# IO60P16.net
KiCad netlist of a schematic drawn in EAGLE
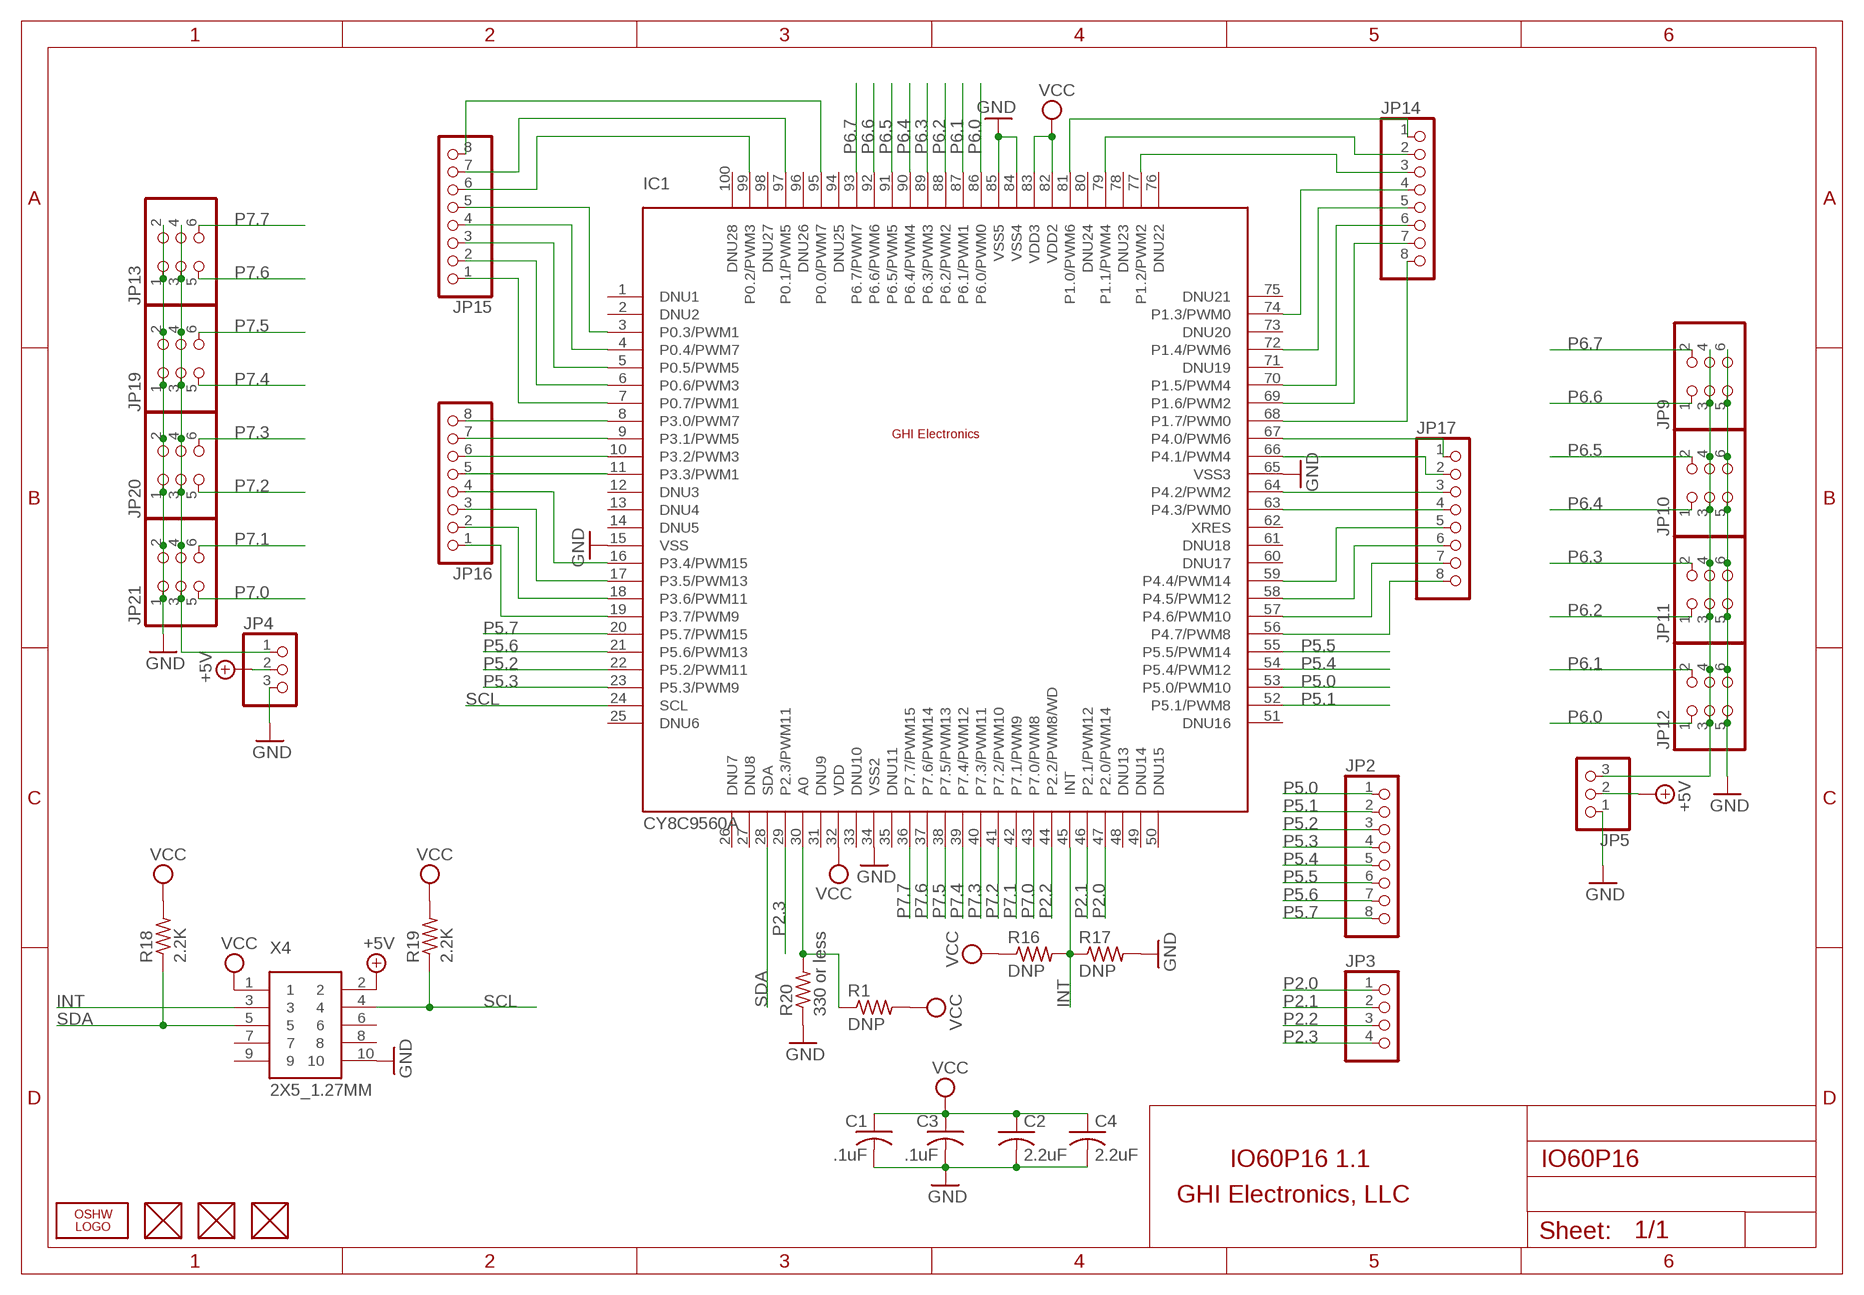
[diagram p0: schematic, sheet 1]

(export (version "E")
  (design (tool "Eeschema 10.0.6"))
  (components
    (comp (ref "C1")
      (value ".1uF")
      (footprint "eagle-import:C0603K")
      (libsource (lib "eagle-import") (part "C-USC0603K"))
    )
    (comp (ref "C2")
      (value "2.2uF")
      (footprint "eagle-import:C0805K")
      (libsource (lib "eagle-import") (part "C-USC0805K"))
    )
    (comp (ref "C3")
      (value ".1uF")
      (footprint "eagle-import:C0603K")
      (libsource (lib "eagle-import") (part "C-USC0603K"))
    )
    (comp (ref "C4")
      (value "2.2uF")
      (footprint "eagle-import:C0805K")
      (libsource (lib "eagle-import") (part "C-USC0805K"))
    )
    (comp (ref "FUD1")
      (value "FIDUCIAL")
      (footprint "eagle-import:FIDUCIAL_40MIL")
      (libsource (lib "eagle-import") (part "FIDUCIAL"))
    )
    (comp (ref "FUD2")
      (value "FIDUCIAL")
      (footprint "eagle-import:FIDUCIAL_40MIL")
      (libsource (lib "eagle-import") (part "FIDUCIAL"))
    )
    (comp (ref "FUD3")
      (value "FIDUCIAL")
      (footprint "eagle-import:FIDUCIAL_40MIL")
      (libsource (lib "eagle-import") (part "FIDUCIAL"))
    )
    (comp (ref "IC1")
      (value "CY8C9560A")
      (footprint "eagle-import:LQFP100")
      (libsource (lib "eagle-import") (part "CY8C9560A"))
    )
    (comp (ref "JP2")
      (value "PINHD-1X8")
      (footprint "eagle-import:1X08")
      (libsource (lib "eagle-import") (part "PINHD-1X8"))
    )
    (comp (ref "JP3")
      (value "PINHD-1X4")
      (footprint "eagle-import:1X04")
      (libsource (lib "eagle-import") (part "PINHD-1X4"))
    )
    (comp (ref "JP4")
      (value "PINHD-1X3")
      (footprint "eagle-import:1X03")
      (libsource (lib "eagle-import") (part "PINHD-1X3"))
    )
    (comp (ref "JP5")
      (value "PINHD-1X3")
      (footprint "eagle-import:1X03")
      (libsource (lib "eagle-import") (part "PINHD-1X3"))
    )
    (comp (ref "JP9")
      (value "PINHD-2X3")
      (footprint "eagle-import:2X03")
      (libsource (lib "eagle-import") (part "PINHD-2X3"))
    )
    (comp (ref "JP10")
      (value "PINHD-2X3")
      (footprint "eagle-import:2X03")
      (libsource (lib "eagle-import") (part "PINHD-2X3"))
    )
    (comp (ref "JP11")
      (value "PINHD-2X3")
      (footprint "eagle-import:2X03")
      (libsource (lib "eagle-import") (part "PINHD-2X3"))
    )
    (comp (ref "JP12")
      (value "PINHD-2X3")
      (footprint "eagle-import:2X03")
      (libsource (lib "eagle-import") (part "PINHD-2X3"))
    )
    (comp (ref "JP13")
      (value "PINHD-2X3")
      (footprint "eagle-import:2X03")
      (libsource (lib "eagle-import") (part "PINHD-2X3"))
    )
    (comp (ref "JP14")
      (value "PINHD-1X8")
      (footprint "eagle-import:1X08")
      (libsource (lib "eagle-import") (part "PINHD-1X8"))
    )
    (comp (ref "JP15")
      (value "PINHD-1X8")
      (footprint "eagle-import:1X08")
      (libsource (lib "eagle-import") (part "PINHD-1X8"))
    )
    (comp (ref "JP16")
      (value "PINHD-1X8")
      (footprint "eagle-import:1X08")
      (libsource (lib "eagle-import") (part "PINHD-1X8"))
    )
    (comp (ref "JP17")
      (value "PINHD-1X8")
      (footprint "eagle-import:1X08")
      (libsource (lib "eagle-import") (part "PINHD-1X8"))
    )
    (comp (ref "JP19")
      (value "PINHD-2X3")
      (footprint "eagle-import:2X03")
      (libsource (lib "eagle-import") (part "PINHD-2X3"))
    )
    (comp (ref "JP20")
      (value "PINHD-2X3")
      (footprint "eagle-import:2X03")
      (libsource (lib "eagle-import") (part "PINHD-2X3"))
    )
    (comp (ref "JP21")
      (value "PINHD-2X3")
      (footprint "eagle-import:2X03")
      (libsource (lib "eagle-import") (part "PINHD-2X3"))
    )
    (comp (ref "LOGO1")
      (value "LOGO-OSHW-FILLX0200-NT")
      (footprint "eagle-import:OSHW_FILLX200_NOTEXT")
      (libsource (lib "eagle-import") (part "LOGO-OSHW-FILLX0200-NT"))
    )
    (comp (ref "R1")
      (value "DNP")
      (footprint "eagle-import:R0603")
      (libsource (lib "eagle-import") (part "R-US_R0603"))
    )
    (comp (ref "R16")
      (value "DNP")
      (footprint "eagle-import:R0603")
      (libsource (lib "eagle-import") (part "R-US_R0603"))
    )
    (comp (ref "R17")
      (value "DNP")
      (footprint "eagle-import:R0603")
      (libsource (lib "eagle-import") (part "R-US_R0603"))
    )
    (comp (ref "R18")
      (value "2.2K")
      (footprint "eagle-import:R0603")
      (libsource (lib "eagle-import") (part "R-US_R0603"))
    )
    (comp (ref "R19")
      (value "2.2K")
      (footprint "eagle-import:R0603")
      (libsource (lib "eagle-import") (part "R-US_R0603"))
    )
    (comp (ref "R20")
      (value "330 or less")
      (footprint "eagle-import:R0603")
      (libsource (lib "eagle-import") (part "R-US_R0603"))
    )
    (comp (ref "X4")
      (value "2X5_1.27MM")
      (footprint "eagle-import:2X5_1.27MM")
      (libsource (lib "eagle-import") (part "2X5_1.27MM"))
    )
  )
  (nets
    (net (code "1") (name "+5V") (class "Default")
      (node (ref "JP4") (pin "2") (pinfunction "2_2") (pintype "passive"))
      (node (ref "JP5") (pin "2") (pinfunction "2_2") (pintype "passive"))
      (node (ref "X4") (pin "2") (pinfunction "2_2") (pintype "bidirectional"))
    )
    (net (code "2") (name "/INT") (class "Default")
      (node (ref "IC1") (pin "45") (pinfunction "INT_45") (pintype "bidirectional"))
      (node (ref "R16") (pin "2") (pinfunction "2_2") (pintype "passive"))
      (node (ref "R17") (pin "1") (pinfunction "1_1") (pintype "passive"))
      (node (ref "X4") (pin "3") (pinfunction "3_3") (pintype "bidirectional"))
    )
    (net (code "3") (name "/P2.0") (class "Default")
      (node (ref "IC1") (pin "47") (pinfunction "P2.0/PWM14_47") (pintype "bidirectional"))
      (node (ref "JP3") (pin "1") (pinfunction "1_1") (pintype "passive"))
    )
    (net (code "4") (name "/P2.1") (class "Default")
      (node (ref "IC1") (pin "46") (pinfunction "P2.1/PWM12_46") (pintype "bidirectional"))
      (node (ref "JP3") (pin "2") (pinfunction "2_2") (pintype "passive"))
    )
    (net (code "5") (name "/P2.2") (class "Default")
      (node (ref "IC1") (pin "44") (pinfunction "P2.2/PWM8/WD_44") (pintype "bidirectional"))
      (node (ref "JP3") (pin "3") (pinfunction "3_3") (pintype "passive"))
    )
    (net (code "6") (name "/P2.3") (class "Default")
      (node (ref "IC1") (pin "29") (pinfunction "P2.3/PWM11_29") (pintype "bidirectional"))
      (node (ref "JP3") (pin "4") (pinfunction "4_4") (pintype "passive"))
    )
    (net (code "7") (name "/P5.0") (class "Default")
      (node (ref "IC1") (pin "53") (pinfunction "P5.0/PWM10_53") (pintype "bidirectional"))
      (node (ref "JP2") (pin "1") (pinfunction "1_1") (pintype "passive"))
    )
    (net (code "8") (name "/P5.1") (class "Default")
      (node (ref "IC1") (pin "52") (pinfunction "P5.1/PWM8_52") (pintype "bidirectional"))
      (node (ref "JP2") (pin "2") (pinfunction "2_2") (pintype "passive"))
    )
    (net (code "9") (name "/P5.2") (class "Default")
      (node (ref "IC1") (pin "22") (pinfunction "P5.2/PWM11_22") (pintype "bidirectional"))
      (node (ref "JP2") (pin "3") (pinfunction "3_3") (pintype "passive"))
    )
    (net (code "10") (name "/P5.3") (class "Default")
      (node (ref "IC1") (pin "23") (pinfunction "P5.3/PWM9_23") (pintype "bidirectional"))
      (node (ref "JP2") (pin "4") (pinfunction "4_4") (pintype "passive"))
    )
    (net (code "11") (name "/P5.4") (class "Default")
      (node (ref "IC1") (pin "54") (pinfunction "P5.4/PWM12_54") (pintype "bidirectional"))
      (node (ref "JP2") (pin "5") (pinfunction "5_5") (pintype "passive"))
    )
    (net (code "12") (name "/P5.5") (class "Default")
      (node (ref "IC1") (pin "55") (pinfunction "P5.5/PWM14_55") (pintype "bidirectional"))
      (node (ref "JP2") (pin "6") (pinfunction "6_6") (pintype "passive"))
    )
    (net (code "13") (name "/P5.6") (class "Default")
      (node (ref "IC1") (pin "21") (pinfunction "P5.6/PWM13_21") (pintype "bidirectional"))
      (node (ref "JP2") (pin "7") (pinfunction "7_7") (pintype "passive"))
    )
    (net (code "14") (name "/P5.7") (class "Default")
      (node (ref "IC1") (pin "20") (pinfunction "P5.7/PWM15_20") (pintype "bidirectional"))
      (node (ref "JP2") (pin "8") (pinfunction "8_8") (pintype "passive"))
    )
    (net (code "15") (name "/P6.0") (class "Default")
      (node (ref "IC1") (pin "86") (pinfunction "P6.0/PWM0_86") (pintype "bidirectional"))
      (node (ref "JP12") (pin "1") (pinfunction "1_1") (pintype "passive"))
    )
    (net (code "16") (name "/P6.1") (class "Default")
      (node (ref "IC1") (pin "87") (pinfunction "P6.1/PWM1_87") (pintype "bidirectional"))
      (node (ref "JP12") (pin "2") (pinfunction "2_2") (pintype "passive"))
    )
    (net (code "17") (name "/P6.2") (class "Default")
      (node (ref "IC1") (pin "88") (pinfunction "P6.2/PWM2_88") (pintype "bidirectional"))
      (node (ref "JP11") (pin "1") (pinfunction "1_1") (pintype "passive"))
    )
    (net (code "18") (name "/P6.3") (class "Default")
      (node (ref "IC1") (pin "89") (pinfunction "P6.3/PWM3_89") (pintype "bidirectional"))
      (node (ref "JP11") (pin "2") (pinfunction "2_2") (pintype "passive"))
    )
    (net (code "19") (name "/P6.4") (class "Default")
      (node (ref "IC1") (pin "90") (pinfunction "P6.4/PWM4_90") (pintype "bidirectional"))
      (node (ref "JP10") (pin "1") (pinfunction "1_1") (pintype "passive"))
    )
    (net (code "20") (name "/P6.5") (class "Default")
      (node (ref "IC1") (pin "91") (pinfunction "P6.5/PWM5_91") (pintype "bidirectional"))
      (node (ref "JP10") (pin "2") (pinfunction "2_2") (pintype "passive"))
    )
    (net (code "21") (name "/P6.6") (class "Default")
      (node (ref "IC1") (pin "92") (pinfunction "P6.6/PWM6_92") (pintype "bidirectional"))
      (node (ref "JP9") (pin "1") (pinfunction "1_1") (pintype "passive"))
    )
    (net (code "22") (name "/P6.7") (class "Default")
      (node (ref "IC1") (pin "93") (pinfunction "P6.7/PWM7_93") (pintype "bidirectional"))
      (node (ref "JP9") (pin "2") (pinfunction "2_2") (pintype "passive"))
    )
    (net (code "23") (name "/P7.0") (class "Default")
      (node (ref "IC1") (pin "43") (pinfunction "P7.0/PWM8_43") (pintype "bidirectional"))
      (node (ref "JP21") (pin "5") (pinfunction "5_5") (pintype "passive"))
    )
    (net (code "24") (name "/P7.1") (class "Default")
      (node (ref "IC1") (pin "42") (pinfunction "P7.1/PWM9_42") (pintype "bidirectional"))
      (node (ref "JP21") (pin "6") (pinfunction "6_6") (pintype "passive"))
    )
    (net (code "25") (name "/P7.2") (class "Default")
      (node (ref "IC1") (pin "41") (pinfunction "P7.2/PWM10_41") (pintype "bidirectional"))
      (node (ref "JP20") (pin "5") (pinfunction "5_5") (pintype "passive"))
    )
    (net (code "26") (name "/P7.3") (class "Default")
      (node (ref "IC1") (pin "40") (pinfunction "P7.3/PWM11_40") (pintype "bidirectional"))
      (node (ref "JP20") (pin "6") (pinfunction "6_6") (pintype "passive"))
    )
    (net (code "27") (name "/P7.4") (class "Default")
      (node (ref "IC1") (pin "39") (pinfunction "P7.4/PWM12_39") (pintype "bidirectional"))
      (node (ref "JP19") (pin "5") (pinfunction "5_5") (pintype "passive"))
    )
    (net (code "28") (name "/P7.5") (class "Default")
      (node (ref "IC1") (pin "38") (pinfunction "P7.5/PWM13_38") (pintype "bidirectional"))
      (node (ref "JP19") (pin "6") (pinfunction "6_6") (pintype "passive"))
    )
    (net (code "29") (name "/P7.6") (class "Default")
      (node (ref "IC1") (pin "37") (pinfunction "P7.6/PWM14_37") (pintype "bidirectional"))
      (node (ref "JP13") (pin "5") (pinfunction "5_5") (pintype "passive"))
    )
    (net (code "30") (name "/P7.7") (class "Default")
      (node (ref "IC1") (pin "36") (pinfunction "P7.7/PWM15_36") (pintype "bidirectional"))
      (node (ref "JP13") (pin "6") (pinfunction "6_6") (pintype "passive"))
    )
    (net (code "31") (name "/SCL") (class "Default")
      (node (ref "IC1") (pin "24") (pinfunction "SCL_24") (pintype "bidirectional"))
      (node (ref "R19") (pin "1") (pinfunction "1_1") (pintype "passive"))
      (node (ref "X4") (pin "4") (pinfunction "4_4") (pintype "bidirectional"))
    )
    (net (code "32") (name "/SDA") (class "Default")
      (node (ref "IC1") (pin "28") (pinfunction "SDA_28") (pintype "bidirectional"))
      (node (ref "R18") (pin "1") (pinfunction "1_1") (pintype "passive"))
      (node (ref "X4") (pin "5") (pinfunction "5_5") (pintype "bidirectional"))
    )
    (net (code "33") (name "GND") (class "Default")
      (node (ref "C1") (pin "2") (pinfunction "2_2") (pintype "passive"))
      (node (ref "C2") (pin "2") (pinfunction "2_2") (pintype "passive"))
      (node (ref "C3") (pin "2") (pinfunction "2_2") (pintype "passive"))
      (node (ref "C4") (pin "2") (pinfunction "2_2") (pintype "passive"))
      (node (ref "IC1") (pin "15") (pinfunction "VSS_15") (pintype "bidirectional"))
      (node (ref "IC1") (pin "34") (pinfunction "VSS2_34") (pintype "bidirectional"))
      (node (ref "IC1") (pin "65") (pinfunction "VSS3_65") (pintype "bidirectional"))
      (node (ref "IC1") (pin "84") (pinfunction "VSS4_84") (pintype "bidirectional"))
      (node (ref "IC1") (pin "85") (pinfunction "VSS5_85") (pintype "bidirectional"))
      (node (ref "JP10") (pin "5") (pinfunction "5_5") (pintype "passive"))
      (node (ref "JP10") (pin "6") (pinfunction "6_6") (pintype "passive"))
      (node (ref "JP11") (pin "5") (pinfunction "5_5") (pintype "passive"))
      (node (ref "JP11") (pin "6") (pinfunction "6_6") (pintype "passive"))
      (node (ref "JP12") (pin "5") (pinfunction "5_5") (pintype "passive"))
      (node (ref "JP12") (pin "6") (pinfunction "6_6") (pintype "passive"))
      (node (ref "JP13") (pin "1") (pinfunction "1_1") (pintype "passive"))
      (node (ref "JP13") (pin "2") (pinfunction "2_2") (pintype "passive"))
      (node (ref "JP19") (pin "1") (pinfunction "1_1") (pintype "passive"))
      (node (ref "JP19") (pin "2") (pinfunction "2_2") (pintype "passive"))
      (node (ref "JP20") (pin "1") (pinfunction "1_1") (pintype "passive"))
      (node (ref "JP20") (pin "2") (pinfunction "2_2") (pintype "passive"))
      (node (ref "JP21") (pin "1") (pinfunction "1_1") (pintype "passive"))
      (node (ref "JP21") (pin "2") (pinfunction "2_2") (pintype "passive"))
      (node (ref "JP4") (pin "3") (pinfunction "3_3") (pintype "passive"))
      (node (ref "JP5") (pin "1") (pinfunction "1_1") (pintype "passive"))
      (node (ref "JP9") (pin "5") (pinfunction "5_5") (pintype "passive"))
      (node (ref "JP9") (pin "6") (pinfunction "6_6") (pintype "passive"))
      (node (ref "R17") (pin "2") (pinfunction "2_2") (pintype "passive"))
      (node (ref "R20") (pin "1") (pinfunction "1_1") (pintype "passive"))
      (node (ref "X4") (pin "10") (pinfunction "10_10") (pintype "bidirectional"))
    )
    (net (code "34") (name "Net-(IC1-A0)") (class "Default")
      (node (ref "IC1") (pin "30") (pinfunction "A0_30") (pintype "bidirectional"))
      (node (ref "R1") (pin "1") (pinfunction "1_1") (pintype "passive"))
      (node (ref "R20") (pin "2") (pinfunction "2_2") (pintype "passive"))
    )
    (net (code "35") (name "Net-(IC1-P0.0{slash}PWM7)") (class "Default")
      (node (ref "IC1") (pin "95") (pinfunction "P0.0/PWM7_95") (pintype "bidirectional"))
      (node (ref "JP15") (pin "8") (pinfunction "8_8") (pintype "passive"))
    )
    (net (code "36") (name "Net-(IC1-P0.1{slash}PWM5)") (class "Default")
      (node (ref "IC1") (pin "97") (pinfunction "P0.1/PWM5_97") (pintype "bidirectional"))
      (node (ref "JP15") (pin "7") (pinfunction "7_7") (pintype "passive"))
    )
    (net (code "37") (name "Net-(IC1-P0.2{slash}PWM3)") (class "Default")
      (node (ref "IC1") (pin "99") (pinfunction "P0.2/PWM3_99") (pintype "bidirectional"))
      (node (ref "JP15") (pin "6") (pinfunction "6_6") (pintype "passive"))
    )
    (net (code "38") (name "Net-(IC1-P0.3{slash}PWM1)") (class "Default")
      (node (ref "IC1") (pin "3") (pinfunction "P0.3/PWM1_3") (pintype "bidirectional"))
      (node (ref "JP15") (pin "5") (pinfunction "5_5") (pintype "passive"))
    )
    (net (code "39") (name "Net-(IC1-P0.4{slash}PWM7)") (class "Default")
      (node (ref "IC1") (pin "4") (pinfunction "P0.4/PWM7_4") (pintype "bidirectional"))
      (node (ref "JP15") (pin "4") (pinfunction "4_4") (pintype "passive"))
    )
    (net (code "40") (name "Net-(IC1-P0.5{slash}PWM5)") (class "Default")
      (node (ref "IC1") (pin "5") (pinfunction "P0.5/PWM5_5") (pintype "bidirectional"))
      (node (ref "JP15") (pin "3") (pinfunction "3_3") (pintype "passive"))
    )
    (net (code "41") (name "Net-(IC1-P0.6{slash}PWM3)") (class "Default")
      (node (ref "IC1") (pin "6") (pinfunction "P0.6/PWM3_6") (pintype "bidirectional"))
      (node (ref "JP15") (pin "2") (pinfunction "2_2") (pintype "passive"))
    )
    (net (code "42") (name "Net-(IC1-P0.7{slash}PWM1)") (class "Default")
      (node (ref "IC1") (pin "7") (pinfunction "P0.7/PWM1_7") (pintype "bidirectional"))
      (node (ref "JP15") (pin "1") (pinfunction "1_1") (pintype "passive"))
    )
    (net (code "43") (name "Net-(IC1-P1.0{slash}PWM6)") (class "Default")
      (node (ref "IC1") (pin "81") (pinfunction "P1.0/PWM6_81") (pintype "bidirectional"))
      (node (ref "JP14") (pin "1") (pinfunction "1_1") (pintype "passive"))
    )
    (net (code "44") (name "Net-(IC1-P1.1{slash}PWM4)") (class "Default")
      (node (ref "IC1") (pin "79") (pinfunction "P1.1/PWM4_79") (pintype "bidirectional"))
      (node (ref "JP14") (pin "2") (pinfunction "2_2") (pintype "passive"))
    )
    (net (code "45") (name "Net-(IC1-P1.2{slash}PWM2)") (class "Default")
      (node (ref "IC1") (pin "77") (pinfunction "P1.2/PWM2_77") (pintype "bidirectional"))
      (node (ref "JP14") (pin "3") (pinfunction "3_3") (pintype "passive"))
    )
    (net (code "46") (name "Net-(IC1-P1.3{slash}PWM0)") (class "Default")
      (node (ref "IC1") (pin "74") (pinfunction "P1.3/PWM0_74") (pintype "bidirectional"))
      (node (ref "JP14") (pin "4") (pinfunction "4_4") (pintype "passive"))
    )
    (net (code "47") (name "Net-(IC1-P1.4{slash}PWM6)") (class "Default")
      (node (ref "IC1") (pin "72") (pinfunction "P1.4/PWM6_72") (pintype "bidirectional"))
      (node (ref "JP14") (pin "5") (pinfunction "5_5") (pintype "passive"))
    )
    (net (code "48") (name "Net-(IC1-P1.5{slash}PWM4)") (class "Default")
      (node (ref "IC1") (pin "70") (pinfunction "P1.5/PWM4_70") (pintype "bidirectional"))
      (node (ref "JP14") (pin "6") (pinfunction "6_6") (pintype "passive"))
    )
    (net (code "49") (name "Net-(IC1-P1.6{slash}PWM2)") (class "Default")
      (node (ref "IC1") (pin "69") (pinfunction "P1.6/PWM2_69") (pintype "bidirectional"))
      (node (ref "JP14") (pin "7") (pinfunction "7_7") (pintype "passive"))
    )
    (net (code "50") (name "Net-(IC1-P1.7{slash}PWM0)") (class "Default")
      (node (ref "IC1") (pin "68") (pinfunction "P1.7/PWM0_68") (pintype "bidirectional"))
      (node (ref "JP14") (pin "8") (pinfunction "8_8") (pintype "passive"))
    )
    (net (code "51") (name "Net-(IC1-P3.0{slash}PWM7)") (class "Default")
      (node (ref "IC1") (pin "8") (pinfunction "P3.0/PWM7_8") (pintype "bidirectional"))
      (node (ref "JP16") (pin "8") (pinfunction "8_8") (pintype "passive"))
    )
    (net (code "52") (name "Net-(IC1-P3.1{slash}PWM5)") (class "Default")
      (node (ref "IC1") (pin "9") (pinfunction "P3.1/PWM5_9") (pintype "bidirectional"))
      (node (ref "JP16") (pin "7") (pinfunction "7_7") (pintype "passive"))
    )
    (net (code "53") (name "Net-(IC1-P3.2{slash}PWM3)") (class "Default")
      (node (ref "IC1") (pin "10") (pinfunction "P3.2/PWM3_10") (pintype "bidirectional"))
      (node (ref "JP16") (pin "6") (pinfunction "6_6") (pintype "passive"))
    )
    (net (code "54") (name "Net-(IC1-P3.3{slash}PWM1)") (class "Default")
      (node (ref "IC1") (pin "11") (pinfunction "P3.3/PWM1_11") (pintype "bidirectional"))
      (node (ref "JP16") (pin "5") (pinfunction "5_5") (pintype "passive"))
    )
    (net (code "55") (name "Net-(IC1-P3.4{slash}PWM15)") (class "Default")
      (node (ref "IC1") (pin "16") (pinfunction "P3.4/PWM15_16") (pintype "bidirectional"))
      (node (ref "JP16") (pin "4") (pinfunction "4_4") (pintype "passive"))
    )
    (net (code "56") (name "Net-(IC1-P3.5{slash}PWM13)") (class "Default")
      (node (ref "IC1") (pin "17") (pinfunction "P3.5/PWM13_17") (pintype "bidirectional"))
      (node (ref "JP16") (pin "3") (pinfunction "3_3") (pintype "passive"))
    )
    (net (code "57") (name "Net-(IC1-P3.6{slash}PWM11)") (class "Default")
      (node (ref "IC1") (pin "18") (pinfunction "P3.6/PWM11_18") (pintype "bidirectional"))
      (node (ref "JP16") (pin "2") (pinfunction "2_2") (pintype "passive"))
    )
    (net (code "58") (name "Net-(IC1-P3.7{slash}PWM9)") (class "Default")
      (node (ref "IC1") (pin "19") (pinfunction "P3.7/PWM9_19") (pintype "bidirectional"))
      (node (ref "JP16") (pin "1") (pinfunction "1_1") (pintype "passive"))
    )
    (net (code "59") (name "Net-(IC1-P4.0{slash}PWM6)") (class "Default")
      (node (ref "IC1") (pin "67") (pinfunction "P4.0/PWM6_67") (pintype "bidirectional"))
      (node (ref "JP17") (pin "1") (pinfunction "1_1") (pintype "passive"))
    )
    (net (code "60") (name "Net-(IC1-P4.1{slash}PWM4)") (class "Default")
      (node (ref "IC1") (pin "66") (pinfunction "P4.1/PWM4_66") (pintype "bidirectional"))
      (node (ref "JP17") (pin "2") (pinfunction "2_2") (pintype "passive"))
    )
    (net (code "61") (name "Net-(IC1-P4.2{slash}PWM2)") (class "Default")
      (node (ref "IC1") (pin "64") (pinfunction "P4.2/PWM2_64") (pintype "bidirectional"))
      (node (ref "JP17") (pin "3") (pinfunction "3_3") (pintype "passive"))
    )
    (net (code "62") (name "Net-(IC1-P4.3{slash}PWM0)") (class "Default")
      (node (ref "IC1") (pin "63") (pinfunction "P4.3/PWM0_63") (pintype "bidirectional"))
      (node (ref "JP17") (pin "4") (pinfunction "4_4") (pintype "passive"))
    )
    (net (code "63") (name "Net-(IC1-P4.4{slash}PWM14)") (class "Default")
      (node (ref "IC1") (pin "59") (pinfunction "P4.4/PWM14_59") (pintype "bidirectional"))
      (node (ref "JP17") (pin "5") (pinfunction "5_5") (pintype "passive"))
    )
    (net (code "64") (name "Net-(IC1-P4.5{slash}PWM12)") (class "Default")
      (node (ref "IC1") (pin "58") (pinfunction "P4.5/PWM12_58") (pintype "bidirectional"))
      (node (ref "JP17") (pin "6") (pinfunction "6_6") (pintype "passive"))
    )
    (net (code "65") (name "Net-(IC1-P4.6{slash}PWM10)") (class "Default")
      (node (ref "IC1") (pin "57") (pinfunction "P4.6/PWM10_57") (pintype "bidirectional"))
      (node (ref "JP17") (pin "7") (pinfunction "7_7") (pintype "passive"))
    )
    (net (code "66") (name "Net-(IC1-P4.7{slash}PWM8)") (class "Default")
      (node (ref "IC1") (pin "56") (pinfunction "P4.7/PWM8_56") (pintype "bidirectional"))
      (node (ref "JP17") (pin "8") (pinfunction "8_8") (pintype "passive"))
    )
    (net (code "67") (name "Net-(JP10-Pad3)") (class "Default")
      (node (ref "JP10") (pin "3") (pinfunction "3_3") (pintype "passive"))
      (node (ref "JP10") (pin "4") (pinfunction "4_4") (pintype "passive"))
      (node (ref "JP11") (pin "3") (pinfunction "3_3") (pintype "passive"))
      (node (ref "JP11") (pin "4") (pinfunction "4_4") (pintype "passive"))
      (node (ref "JP12") (pin "3") (pinfunction "3_3") (pintype "passive"))
      (node (ref "JP12") (pin "4") (pinfunction "4_4") (pintype "passive"))
      (node (ref "JP5") (pin "3") (pinfunction "3_3") (pintype "passive"))
      (node (ref "JP9") (pin "3") (pinfunction "3_3") (pintype "passive"))
      (node (ref "JP9") (pin "4") (pinfunction "4_4") (pintype "passive"))
    )
    (net (code "68") (name "Net-(JP13-Pad3)") (class "Default")
      (node (ref "JP13") (pin "3") (pinfunction "3_3") (pintype "passive"))
      (node (ref "JP13") (pin "4") (pinfunction "4_4") (pintype "passive"))
      (node (ref "JP19") (pin "3") (pinfunction "3_3") (pintype "passive"))
      (node (ref "JP19") (pin "4") (pinfunction "4_4") (pintype "passive"))
      (node (ref "JP20") (pin "3") (pinfunction "3_3") (pintype "passive"))
      (node (ref "JP20") (pin "4") (pinfunction "4_4") (pintype "passive"))
      (node (ref "JP21") (pin "3") (pinfunction "3_3") (pintype "passive"))
      (node (ref "JP21") (pin "4") (pinfunction "4_4") (pintype "passive"))
      (node (ref "JP4") (pin "1") (pinfunction "1_1") (pintype "passive"))
    )
    (net (code "69") (name "VCC") (class "Default")
      (node (ref "C1") (pin "1") (pinfunction "1_1") (pintype "passive"))
      (node (ref "C2") (pin "1") (pinfunction "1_1") (pintype "passive"))
      (node (ref "C3") (pin "1") (pinfunction "1_1") (pintype "passive"))
      (node (ref "C4") (pin "1") (pinfunction "1_1") (pintype "passive"))
      (node (ref "IC1") (pin "32") (pinfunction "VDD_32") (pintype "bidirectional"))
      (node (ref "IC1") (pin "82") (pinfunction "VDD2_82") (pintype "bidirectional"))
      (node (ref "IC1") (pin "83") (pinfunction "VDD3_83") (pintype "bidirectional"))
      (node (ref "R1") (pin "2") (pinfunction "2_2") (pintype "passive"))
      (node (ref "R16") (pin "1") (pinfunction "1_1") (pintype "passive"))
      (node (ref "R18") (pin "2") (pinfunction "2_2") (pintype "passive"))
      (node (ref "R19") (pin "2") (pinfunction "2_2") (pintype "passive"))
      (node (ref "X4") (pin "1") (pinfunction "1_1") (pintype "bidirectional"))
    )
    (net (code "70") (name "unconnected-(FUD1-PadP$1)") (class "Default")
      (node (ref "FUD1") (pin "P$1") (pinfunction "P$1_P$1") (pintype "no_connect"))
    )
    (net (code "71") (name "unconnected-(FUD2-PadP$1)") (class "Default")
      (node (ref "FUD2") (pin "P$1") (pinfunction "P$1_P$1") (pintype "no_connect"))
    )
    (net (code "72") (name "unconnected-(FUD3-PadP$1)") (class "Default")
      (node (ref "FUD3") (pin "P$1") (pinfunction "P$1_P$1") (pintype "no_connect"))
    )
    (net (code "73") (name "unconnected-(IC1-DNU1-Pad1)") (class "Default")
      (node (ref "IC1") (pin "1") (pinfunction "DNU1_1") (pintype "bidirectional"))
    )
    (net (code "74") (name "unconnected-(IC1-DNU2-Pad2)") (class "Default")
      (node (ref "IC1") (pin "2") (pinfunction "DNU2_2") (pintype "bidirectional"))
    )
    (net (code "75") (name "unconnected-(IC1-DNU3-Pad12)") (class "Default")
      (node (ref "IC1") (pin "12") (pinfunction "DNU3_12") (pintype "bidirectional"))
    )
    (net (code "76") (name "unconnected-(IC1-DNU4-Pad13)") (class "Default")
      (node (ref "IC1") (pin "13") (pinfunction "DNU4_13") (pintype "bidirectional"))
    )
    (net (code "77") (name "unconnected-(IC1-DNU5-Pad14)") (class "Default")
      (node (ref "IC1") (pin "14") (pinfunction "DNU5_14") (pintype "bidirectional"))
    )
    (net (code "78") (name "unconnected-(IC1-DNU6-Pad25)") (class "Default")
      (node (ref "IC1") (pin "25") (pinfunction "DNU6_25") (pintype "bidirectional"))
    )
    (net (code "79") (name "unconnected-(IC1-DNU7-Pad26)") (class "Default")
      (node (ref "IC1") (pin "26") (pinfunction "DNU7_26") (pintype "bidirectional"))
    )
    (net (code "80") (name "unconnected-(IC1-DNU8-Pad27)") (class "Default")
      (node (ref "IC1") (pin "27") (pinfunction "DNU8_27") (pintype "bidirectional"))
    )
    (net (code "81") (name "unconnected-(IC1-DNU9-Pad31)") (class "Default")
      (node (ref "IC1") (pin "31") (pinfunction "DNU9_31") (pintype "bidirectional"))
    )
    (net (code "82") (name "unconnected-(IC1-DNU10-Pad33)") (class "Default")
      (node (ref "IC1") (pin "33") (pinfunction "DNU10_33") (pintype "bidirectional"))
    )
    (net (code "83") (name "unconnected-(IC1-DNU11-Pad35)") (class "Default")
      (node (ref "IC1") (pin "35") (pinfunction "DNU11_35") (pintype "bidirectional"))
    )
    (net (code "84") (name "unconnected-(IC1-DNU13-Pad48)") (class "Default")
      (node (ref "IC1") (pin "48") (pinfunction "DNU13_48") (pintype "bidirectional"))
    )
    (net (code "85") (name "unconnected-(IC1-DNU14-Pad49)") (class "Default")
      (node (ref "IC1") (pin "49") (pinfunction "DNU14_49") (pintype "bidirectional"))
    )
    (net (code "86") (name "unconnected-(IC1-DNU15-Pad50)") (class "Default")
      (node (ref "IC1") (pin "50") (pinfunction "DNU15_50") (pintype "bidirectional"))
    )
    (net (code "87") (name "unconnected-(IC1-DNU16-Pad51)") (class "Default")
      (node (ref "IC1") (pin "51") (pinfunction "DNU16_51") (pintype "bidirectional"))
    )
    (net (code "88") (name "unconnected-(IC1-DNU17-Pad60)") (class "Default")
      (node (ref "IC1") (pin "60") (pinfunction "DNU17_60") (pintype "bidirectional"))
    )
    (net (code "89") (name "unconnected-(IC1-DNU18-Pad61)") (class "Default")
      (node (ref "IC1") (pin "61") (pinfunction "DNU18_61") (pintype "bidirectional"))
    )
    (net (code "90") (name "unconnected-(IC1-DNU19-Pad71)") (class "Default")
      (node (ref "IC1") (pin "71") (pinfunction "DNU19_71") (pintype "bidirectional"))
    )
    (net (code "91") (name "unconnected-(IC1-DNU20-Pad73)") (class "Default")
      (node (ref "IC1") (pin "73") (pinfunction "DNU20_73") (pintype "bidirectional"))
    )
    (net (code "92") (name "unconnected-(IC1-DNU21-Pad75)") (class "Default")
      (node (ref "IC1") (pin "75") (pinfunction "DNU21_75") (pintype "bidirectional"))
    )
    (net (code "93") (name "unconnected-(IC1-DNU22-Pad76)") (class "Default")
      (node (ref "IC1") (pin "76") (pinfunction "DNU22_76") (pintype "bidirectional"))
    )
    (net (code "94") (name "unconnected-(IC1-DNU23-Pad78)") (class "Default")
      (node (ref "IC1") (pin "78") (pinfunction "DNU23_78") (pintype "bidirectional"))
    )
    (net (code "95") (name "unconnected-(IC1-DNU24-Pad80)") (class "Default")
      (node (ref "IC1") (pin "80") (pinfunction "DNU24_80") (pintype "bidirectional"))
    )
    (net (code "96") (name "unconnected-(IC1-DNU25-Pad94)") (class "Default")
      (node (ref "IC1") (pin "94") (pinfunction "DNU25_94") (pintype "bidirectional"))
    )
    (net (code "97") (name "unconnected-(IC1-DNU26-Pad96)") (class "Default")
      (node (ref "IC1") (pin "96") (pinfunction "DNU26_96") (pintype "bidirectional"))
    )
    (net (code "98") (name "unconnected-(IC1-DNU27-Pad98)") (class "Default")
      (node (ref "IC1") (pin "98") (pinfunction "DNU27_98") (pintype "bidirectional"))
    )
    (net (code "99") (name "unconnected-(IC1-DNU28-Pad100)") (class "Default")
      (node (ref "IC1") (pin "100") (pinfunction "DNU28_100") (pintype "bidirectional"))
    )
    (net (code "100") (name "unconnected-(IC1-XRES-Pad62)") (class "Default")
      (node (ref "IC1") (pin "62") (pinfunction "XRES_62") (pintype "bidirectional"))
    )
    (net (code "101") (name "unconnected-(X4-Pad6)") (class "Default")
      (node (ref "X4") (pin "6") (pinfunction "6_6") (pintype "bidirectional"))
    )
    (net (code "102") (name "unconnected-(X4-Pad7)") (class "Default")
      (node (ref "X4") (pin "7") (pinfunction "7_7") (pintype "bidirectional"))
    )
    (net (code "103") (name "unconnected-(X4-Pad8)") (class "Default")
      (node (ref "X4") (pin "8") (pinfunction "8_8") (pintype "bidirectional"))
    )
    (net (code "104") (name "unconnected-(X4-Pad9)") (class "Default")
      (node (ref "X4") (pin "9") (pinfunction "9_9") (pintype "bidirectional"))
    )
  )
)
